# Control.net
KiCad netlist of a schematic drawn in Altium Designer
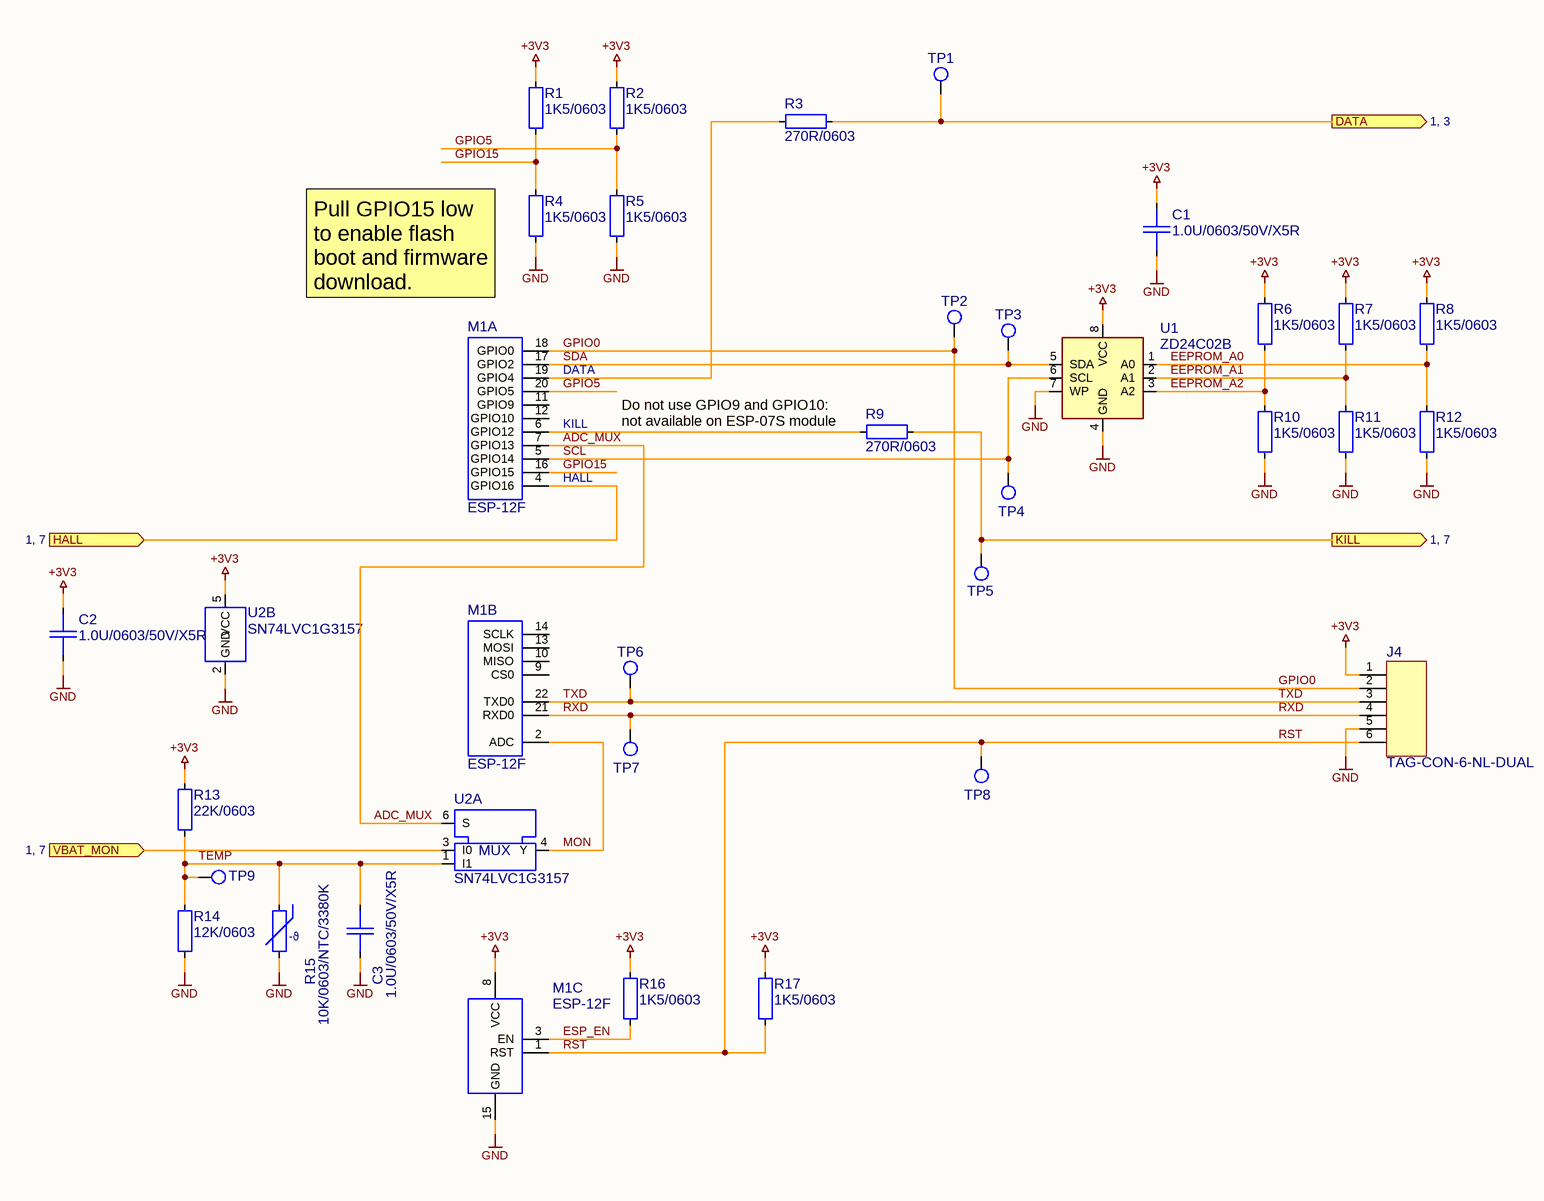
[diagram p0: Control.SchDoc]

(export (version "E")
  (design (tool "Eeschema 10.0.6"))
  (components
    (comp (ref "C1")
      (value "1.0U/0603/50V/X5R")
      (footprint "CAP0603_X7R")
      (description "CAP SM 0603 1.0uF 50V X5R")
      (fields (field (name "MANUFACTURER") "GENERIC"))
      (libsource (lib "daniw_altium_lib") (part "C"))
    )
    (comp (ref "C2")
      (value "1.0U/0603/50V/X5R")
      (footprint "CAP0603_X7R")
      (description "CAP SM 0603 1.0uF 50V X5R")
      (fields (field (name "MANUFACTURER") "GENERIC"))
      (libsource (lib "daniw_altium_lib") (part "C"))
    )
    (comp (ref "C3")
      (value "1.0U/0603/50V/X5R")
      (footprint "CAP0603_X7R")
      (description "CAP SM 0603 1.0uF 50V X5R")
      (fields (field (name "MANUFACTURER") "GENERIC"))
      (libsource (lib "daniw_altium_lib") (part "C"))
    )
    (comp (ref "J4")
      (value "TAG-CON-6-NL-DUAL")
      (footprint "TC2030-NL-2")
      (description "Tag-Connect 2030-NL, 6 pins, no legs, two-sided")
      (fields (field (name "MANUFACTURER") "TAG-CONNECT"))
      (libsource (lib "daniw_altium_lib") (part "CON6"))
    )
    (comp (ref "M1")
      (value "ESP-12F")
      (footprint "ESP-12F")
      (description "ESP8266 based Module with 4MByte Storage")
      (fields (field (name "MANUFACTURER") "AI-Thinker"))
      (libsource (lib "daniw_altium_lib") (part "ESP-12F"))
    )
    (comp (ref "R1")
      (value "1K5/0603")
      (footprint "R0603-0.40-WW")
      (description "RES SM 0603 1K5")
      (fields (field (name "MANUFACTURER") "GENERIC"))
      (libsource (lib "daniw_altium_lib") (part "R"))
    )
    (comp (ref "R2")
      (value "1K5/0603")
      (footprint "R0603-0.40-WW")
      (description "RES SM 0603 1K5")
      (fields (field (name "MANUFACTURER") "GENERIC"))
      (libsource (lib "daniw_altium_lib") (part "R"))
    )
    (comp (ref "R3")
      (value "270R/0603")
      (footprint "R0603-0.40-WW")
      (description "RES SM 0603 270R")
      (fields (field (name "MANUFACTURER") "GENERIC"))
      (libsource (lib "daniw_altium_lib") (part "R"))
    )
    (comp (ref "R4")
      (value "1K5/0603")
      (footprint "R0603-0.40-WW")
      (description "RES SM 0603 1K5")
      (fields (field (name "MANUFACTURER") "GENERIC"))
      (libsource (lib "daniw_altium_lib") (part "R"))
    )
    (comp (ref "R5")
      (value "1K5/0603")
      (footprint "R0603-0.40-WW")
      (description "RES SM 0603 1K5")
      (fields (field (name "MANUFACTURER") "GENERIC"))
      (libsource (lib "daniw_altium_lib") (part "R"))
    )
    (comp (ref "R6")
      (value "1K5/0603")
      (footprint "R0603-0.40-WW")
      (description "RES SM 0603 1K5")
      (fields (field (name "MANUFACTURER") "GENERIC"))
      (libsource (lib "daniw_altium_lib") (part "R"))
    )
    (comp (ref "R7")
      (value "1K5/0603")
      (footprint "R0603-0.40-WW")
      (description "RES SM 0603 1K5")
      (fields (field (name "MANUFACTURER") "GENERIC"))
      (libsource (lib "daniw_altium_lib") (part "R"))
    )
    (comp (ref "R8")
      (value "1K5/0603")
      (footprint "R0603-0.40-WW")
      (description "RES SM 0603 1K5")
      (fields (field (name "MANUFACTURER") "GENERIC"))
      (libsource (lib "daniw_altium_lib") (part "R"))
    )
    (comp (ref "R9")
      (value "270R/0603")
      (footprint "R0603-0.40-WW")
      (description "RES SM 0603 270R")
      (fields (field (name "MANUFACTURER") "GENERIC"))
      (libsource (lib "daniw_altium_lib") (part "R"))
    )
    (comp (ref "R10")
      (value "1K5/0603")
      (footprint "R0603-0.40-WW")
      (description "RES SM 0603 1K5")
      (fields (field (name "MANUFACTURER") "GENERIC"))
      (libsource (lib "daniw_altium_lib") (part "R"))
    )
    (comp (ref "R11")
      (value "1K5/0603")
      (footprint "R0603-0.40-WW")
      (description "RES SM 0603 1K5")
      (fields (field (name "MANUFACTURER") "GENERIC"))
      (libsource (lib "daniw_altium_lib") (part "R"))
    )
    (comp (ref "R12")
      (value "1K5/0603")
      (footprint "R0603-0.40-WW")
      (description "RES SM 0603 1K5")
      (fields (field (name "MANUFACTURER") "GENERIC"))
      (libsource (lib "daniw_altium_lib") (part "R"))
    )
    (comp (ref "R13")
      (value "22K/0603")
      (footprint "R0603-0.40-WW")
      (description "RES SM 0603 22K")
      (fields (field (name "MANUFACTURER") "GENERIC"))
      (libsource (lib "daniw_altium_lib") (part "R"))
    )
    (comp (ref "R14")
      (value "12K/0603")
      (footprint "R0603-0.40-WW")
      (description "RES SM 0603 12K")
      (fields (field (name "MANUFACTURER") "GENERIC"))
      (libsource (lib "daniw_altium_lib") (part "R"))
    )
    (comp (ref "R15")
      (value "10K/0603/NTC/3380K")
      (footprint "R0603-0.40-WW")
      (description "RES NTC SM 0603 10K")
      (fields (field (name "MANUFACTURER") "GENERIC"))
      (libsource (lib "daniw_altium_lib") (part "R_NTC"))
    )
    (comp (ref "R16")
      (value "1K5/0603")
      (footprint "R0603-0.40-WW")
      (description "RES SM 0603 1K5")
      (fields (field (name "MANUFACTURER") "GENERIC"))
      (libsource (lib "daniw_altium_lib") (part "R"))
    )
    (comp (ref "R17")
      (value "1K5/0603")
      (footprint "R0603-0.40-WW")
      (description "RES SM 0603 1K5")
      (fields (field (name "MANUFACTURER") "GENERIC"))
      (libsource (lib "daniw_altium_lib") (part "R"))
    )
    (comp (ref "TP1")
      (value "TP_THD_1.5/0.8")
      (footprint "TP_THD_1.5/0.8")
      (description "THT Test Point 1.5/0.8mm")
      (fields (field (name "MANUFACTURER") "NONE"))
      (libsource (lib "daniw_altium_lib") (part "Testpoint"))
    )
    (comp (ref "TP2")
      (value "TP_THD_1.5/0.8")
      (footprint "TP_THD_1.5/0.8")
      (description "THT Test Point 1.5/0.8mm")
      (fields (field (name "MANUFACTURER") "NONE"))
      (libsource (lib "daniw_altium_lib") (part "Testpoint"))
    )
    (comp (ref "TP3")
      (value "TP_THD_1.5/0.8")
      (footprint "TP_THD_1.5/0.8")
      (description "THT Test Point 1.5/0.8mm")
      (fields (field (name "MANUFACTURER") "NONE"))
      (libsource (lib "daniw_altium_lib") (part "Testpoint"))
    )
    (comp (ref "TP4")
      (value "TP_THD_1.5/0.8")
      (footprint "TP_THD_1.5/0.8")
      (description "THT Test Point 1.5/0.8mm")
      (fields (field (name "MANUFACTURER") "NONE"))
      (libsource (lib "daniw_altium_lib") (part "Testpoint"))
    )
    (comp (ref "TP5")
      (value "TP_THD_1.5/0.8")
      (footprint "TP_THD_1.5/0.8")
      (description "THT Test Point 1.5/0.8mm")
      (fields (field (name "MANUFACTURER") "NONE"))
      (libsource (lib "daniw_altium_lib") (part "Testpoint"))
    )
    (comp (ref "TP6")
      (value "TP_THD_1.5/0.8")
      (footprint "TP_THD_1.5/0.8")
      (description "THT Test Point 1.5/0.8mm")
      (fields (field (name "MANUFACTURER") "NONE"))
      (libsource (lib "daniw_altium_lib") (part "Testpoint"))
    )
    (comp (ref "TP7")
      (value "TP_THD_1.5/0.8")
      (footprint "TP_THD_1.5/0.8")
      (description "THT Test Point 1.5/0.8mm")
      (fields (field (name "MANUFACTURER") "NONE"))
      (libsource (lib "daniw_altium_lib") (part "Testpoint"))
    )
    (comp (ref "TP8")
      (value "TP_THD_1.5/0.8")
      (footprint "TP_THD_1.5/0.8")
      (description "THT Test Point 1.5/0.8mm")
      (fields (field (name "MANUFACTURER") "NONE"))
      (libsource (lib "daniw_altium_lib") (part "Testpoint"))
    )
    (comp (ref "TP9")
      (value "TP_THD_1.5/0.8")
      (footprint "TP_THD_1.5/0.8")
      (description "THT Test Point 1.5/0.8mm")
      (fields (field (name "MANUFACTURER") "NONE"))
      (libsource (lib "daniw_altium_lib") (part "Testpoint"))
    )
    (comp (ref "U1")
      (value "ZD24C02B")
      (footprint "SOP127P600X155-8-SW")
      (description "I2C-Compatible (2-wire) Serial EEPROM 2K bits")
      (fields (field (name "MANUFACTURER") "Zetta"))
      (libsource (lib "daniw_altium_lib") (part "EEPROM_I2C_WP_3ADDR"))
    )
    (comp (ref "U2")
      (value "SN74LVC1G3157")
      (footprint "SOT65P210X95-6-SE")
      (description "Single-Pole-Double-Throw Analog Switch")
      (fields (field (name "MANUFACTURER") "TI"))
      (libsource (lib "daniw_altium_lib") (part "MUX 1X2-1"))
    )
  )
  (nets
    (net (code "1") (name "+3V3") (class "Default")
      (node (ref "C1") (pin "1") (pinfunction "1_1") (pintype "passive"))
      (node (ref "C2") (pin "1") (pinfunction "1_1") (pintype "passive"))
      (node (ref "J4") (pin "1") (pintype "passive"))
      (node (ref "M1") (pin "8") (pinfunction "VCC_8") (pintype "passive"))
      (node (ref "R1") (pin "1") (pinfunction "1_1") (pintype "passive"))
      (node (ref "R13") (pin "1") (pinfunction "1_1") (pintype "passive"))
      (node (ref "R16") (pin "1") (pinfunction "1_1") (pintype "passive"))
      (node (ref "R17") (pin "1") (pinfunction "1_1") (pintype "passive"))
      (node (ref "R2") (pin "1") (pinfunction "1_1") (pintype "passive"))
      (node (ref "R6") (pin "1") (pinfunction "1_1") (pintype "passive"))
      (node (ref "R7") (pin "1") (pinfunction "1_1") (pintype "passive"))
      (node (ref "R8") (pin "1") (pinfunction "1_1") (pintype "passive"))
      (node (ref "U1") (pin "8") (pinfunction "VCC_8") (pintype "passive"))
      (node (ref "U2") (pin "5") (pinfunction "VCC_5") (pintype "passive"))
    )
    (net (code "2") (name "/ADC_MUX") (class "Default")
      (node (ref "M1") (pin "7") (pinfunction "GPIO13_7") (pintype "passive"))
      (node (ref "U2") (pin "6") (pinfunction "S_6") (pintype "passive"))
    )
    (net (code "3") (name "/DATA") (class "Default")
      (node (ref "R3") (pin "2") (pinfunction "2_2") (pintype "passive"))
      (node (ref "TP1") (pin "1") (pinfunction "1_1") (pintype "passive"))
    )
    (net (code "4") (name "/EEPROM_A0") (class "Default")
      (node (ref "R12") (pin "1") (pinfunction "1_1") (pintype "passive"))
      (node (ref "R8") (pin "2") (pinfunction "2_2") (pintype "passive"))
      (node (ref "U1") (pin "1") (pinfunction "A0_1") (pintype "passive"))
    )
    (net (code "5") (name "/EEPROM_A1") (class "Default")
      (node (ref "R11") (pin "1") (pinfunction "1_1") (pintype "passive"))
      (node (ref "R7") (pin "2") (pinfunction "2_2") (pintype "passive"))
      (node (ref "U1") (pin "2") (pinfunction "A1_2") (pintype "passive"))
    )
    (net (code "6") (name "/EEPROM_A2") (class "Default")
      (node (ref "R10") (pin "1") (pinfunction "1_1") (pintype "passive"))
      (node (ref "R6") (pin "2") (pinfunction "2_2") (pintype "passive"))
      (node (ref "U1") (pin "3") (pinfunction "A2_3") (pintype "passive"))
    )
    (net (code "7") (name "/ESP_EN") (class "Default")
      (node (ref "M1") (pin "3") (pinfunction "EN_3") (pintype "passive"))
      (node (ref "R16") (pin "2") (pinfunction "2_2") (pintype "passive"))
    )
    (net (code "8") (name "/GPIO0") (class "Default")
      (node (ref "J4") (pin "2") (pintype "passive"))
      (node (ref "M1") (pin "18") (pinfunction "GPIO0_18") (pintype "passive"))
      (node (ref "TP2") (pin "1") (pinfunction "1_1") (pintype "passive"))
    )
    (net (code "9") (name "/GPIO5") (class "Default")
      (node (ref "M1") (pin "20") (pinfunction "GPIO5_20") (pintype "passive"))
      (node (ref "R2") (pin "2") (pinfunction "2_2") (pintype "passive"))
      (node (ref "R5") (pin "1") (pinfunction "1_1") (pintype "passive"))
    )
    (net (code "10") (name "/GPIO15") (class "Default")
      (node (ref "M1") (pin "16") (pinfunction "GPIO15_16") (pintype "passive"))
      (node (ref "R1") (pin "2") (pinfunction "2_2") (pintype "passive"))
      (node (ref "R4") (pin "1") (pinfunction "1_1") (pintype "passive"))
    )
    (net (code "11") (name "/HALL") (class "Default")
      (node (ref "M1") (pin "4") (pinfunction "GPIO16_4") (pintype "passive"))
    )
    (net (code "12") (name "/KILL") (class "Default")
      (node (ref "R9") (pin "2") (pinfunction "2_2") (pintype "passive"))
      (node (ref "TP5") (pin "1") (pinfunction "1_1") (pintype "passive"))
    )
    (net (code "13") (name "/MON") (class "Default")
      (node (ref "M1") (pin "2") (pinfunction "ADC_2") (pintype "passive"))
      (node (ref "U2") (pin "4") (pinfunction "Y_4") (pintype "passive"))
    )
    (net (code "14") (name "/RST") (class "Default")
      (node (ref "J4") (pin "6") (pintype "passive"))
      (node (ref "M1") (pin "1") (pinfunction "RST_1") (pintype "passive"))
      (node (ref "R17") (pin "2") (pinfunction "2_2") (pintype "passive"))
      (node (ref "TP8") (pin "1") (pinfunction "1_1") (pintype "passive"))
    )
    (net (code "15") (name "/RXD") (class "Default")
      (node (ref "J4") (pin "4") (pintype "passive"))
      (node (ref "M1") (pin "21") (pinfunction "RXD0_21") (pintype "passive"))
      (node (ref "TP7") (pin "1") (pinfunction "1_1") (pintype "passive"))
    )
    (net (code "16") (name "/SCL") (class "Default")
      (node (ref "M1") (pin "5") (pinfunction "GPIO14_5") (pintype "passive"))
      (node (ref "TP4") (pin "1") (pinfunction "1_1") (pintype "passive"))
      (node (ref "U1") (pin "6") (pinfunction "SCL_6") (pintype "passive"))
    )
    (net (code "17") (name "/SDA") (class "Default")
      (node (ref "M1") (pin "17") (pinfunction "GPIO2_17") (pintype "passive"))
      (node (ref "TP3") (pin "1") (pinfunction "1_1") (pintype "passive"))
      (node (ref "U1") (pin "5") (pinfunction "SDA_5") (pintype "passive"))
    )
    (net (code "18") (name "/TEMP") (class "Default")
      (node (ref "C3") (pin "1") (pinfunction "1_1") (pintype "passive"))
      (node (ref "R13") (pin "2") (pinfunction "2_2") (pintype "passive"))
      (node (ref "R14") (pin "1") (pinfunction "1_1") (pintype "passive"))
      (node (ref "R15") (pin "1") (pinfunction "1_1") (pintype "passive"))
      (node (ref "TP9") (pin "1") (pinfunction "1_1") (pintype "passive"))
      (node (ref "U2") (pin "1") (pinfunction "I1_1") (pintype "passive"))
    )
    (net (code "19") (name "/TXD") (class "Default")
      (node (ref "J4") (pin "3") (pintype "passive"))
      (node (ref "M1") (pin "22") (pinfunction "TXD0_22") (pintype "passive"))
      (node (ref "TP6") (pin "1") (pinfunction "1_1") (pintype "passive"))
    )
    (net (code "20") (name "/VBAT_MON") (class "Default")
      (node (ref "U2") (pin "3") (pinfunction "I0_3") (pintype "passive"))
    )
    (net (code "21") (name "GND") (class "Default")
      (node (ref "C1") (pin "2") (pinfunction "2_2") (pintype "passive"))
      (node (ref "C2") (pin "2") (pinfunction "2_2") (pintype "passive"))
      (node (ref "C3") (pin "2") (pinfunction "2_2") (pintype "passive"))
      (node (ref "J4") (pin "5") (pintype "passive"))
      (node (ref "M1") (pin "15") (pinfunction "GND_15") (pintype "passive"))
      (node (ref "R10") (pin "2") (pinfunction "2_2") (pintype "passive"))
      (node (ref "R11") (pin "2") (pinfunction "2_2") (pintype "passive"))
      (node (ref "R12") (pin "2") (pinfunction "2_2") (pintype "passive"))
      (node (ref "R14") (pin "2") (pinfunction "2_2") (pintype "passive"))
      (node (ref "R15") (pin "2") (pinfunction "2_2") (pintype "passive"))
      (node (ref "R4") (pin "2") (pinfunction "2_2") (pintype "passive"))
      (node (ref "R5") (pin "2") (pinfunction "2_2") (pintype "passive"))
      (node (ref "U1") (pin "4") (pinfunction "GND_4") (pintype "passive"))
      (node (ref "U1") (pin "7") (pinfunction "WP_7") (pintype "passive"))
      (node (ref "U2") (pin "2") (pinfunction "GND_2") (pintype "passive"))
    )
    (net (code "22") (name "Net-(M1A-GPIO4)") (class "Default")
      (node (ref "M1") (pin "19") (pinfunction "GPIO4_19") (pintype "passive"))
      (node (ref "R3") (pin "1") (pinfunction "1_1") (pintype "passive"))
    )
    (net (code "23") (name "Net-(M1A-GPIO12)") (class "Default")
      (node (ref "M1") (pin "6") (pinfunction "GPIO12_6") (pintype "passive"))
      (node (ref "R9") (pin "1") (pinfunction "1_1") (pintype "passive"))
    )
    (net (code "24") (name "unconnected-(M1A-GPIO9-Pad11)") (class "Default")
      (node (ref "M1") (pin "11") (pinfunction "GPIO9_11") (pintype "passive"))
    )
    (net (code "25") (name "unconnected-(M1A-GPIO10-Pad12)") (class "Default")
      (node (ref "M1") (pin "12") (pinfunction "GPIO10_12") (pintype "passive"))
    )
    (net (code "26") (name "unconnected-(M1B-CS0-Pad9)") (class "Default")
      (node (ref "M1") (pin "9") (pinfunction "CS0_9") (pintype "passive"))
    )
    (net (code "27") (name "unconnected-(M1B-MISO-Pad10)") (class "Default")
      (node (ref "M1") (pin "10") (pinfunction "MISO_10") (pintype "passive"))
    )
    (net (code "28") (name "unconnected-(M1B-MOSI-Pad13)") (class "Default")
      (node (ref "M1") (pin "13") (pinfunction "MOSI_13") (pintype "passive"))
    )
    (net (code "29") (name "unconnected-(M1B-SCLK-Pad14)") (class "Default")
      (node (ref "M1") (pin "14") (pinfunction "SCLK_14") (pintype "passive"))
    )
  )
)
